# flashlight-driver_2020-10-08_16-01-53.net
KiCad netlist of a schematic drawn in EasyEDA
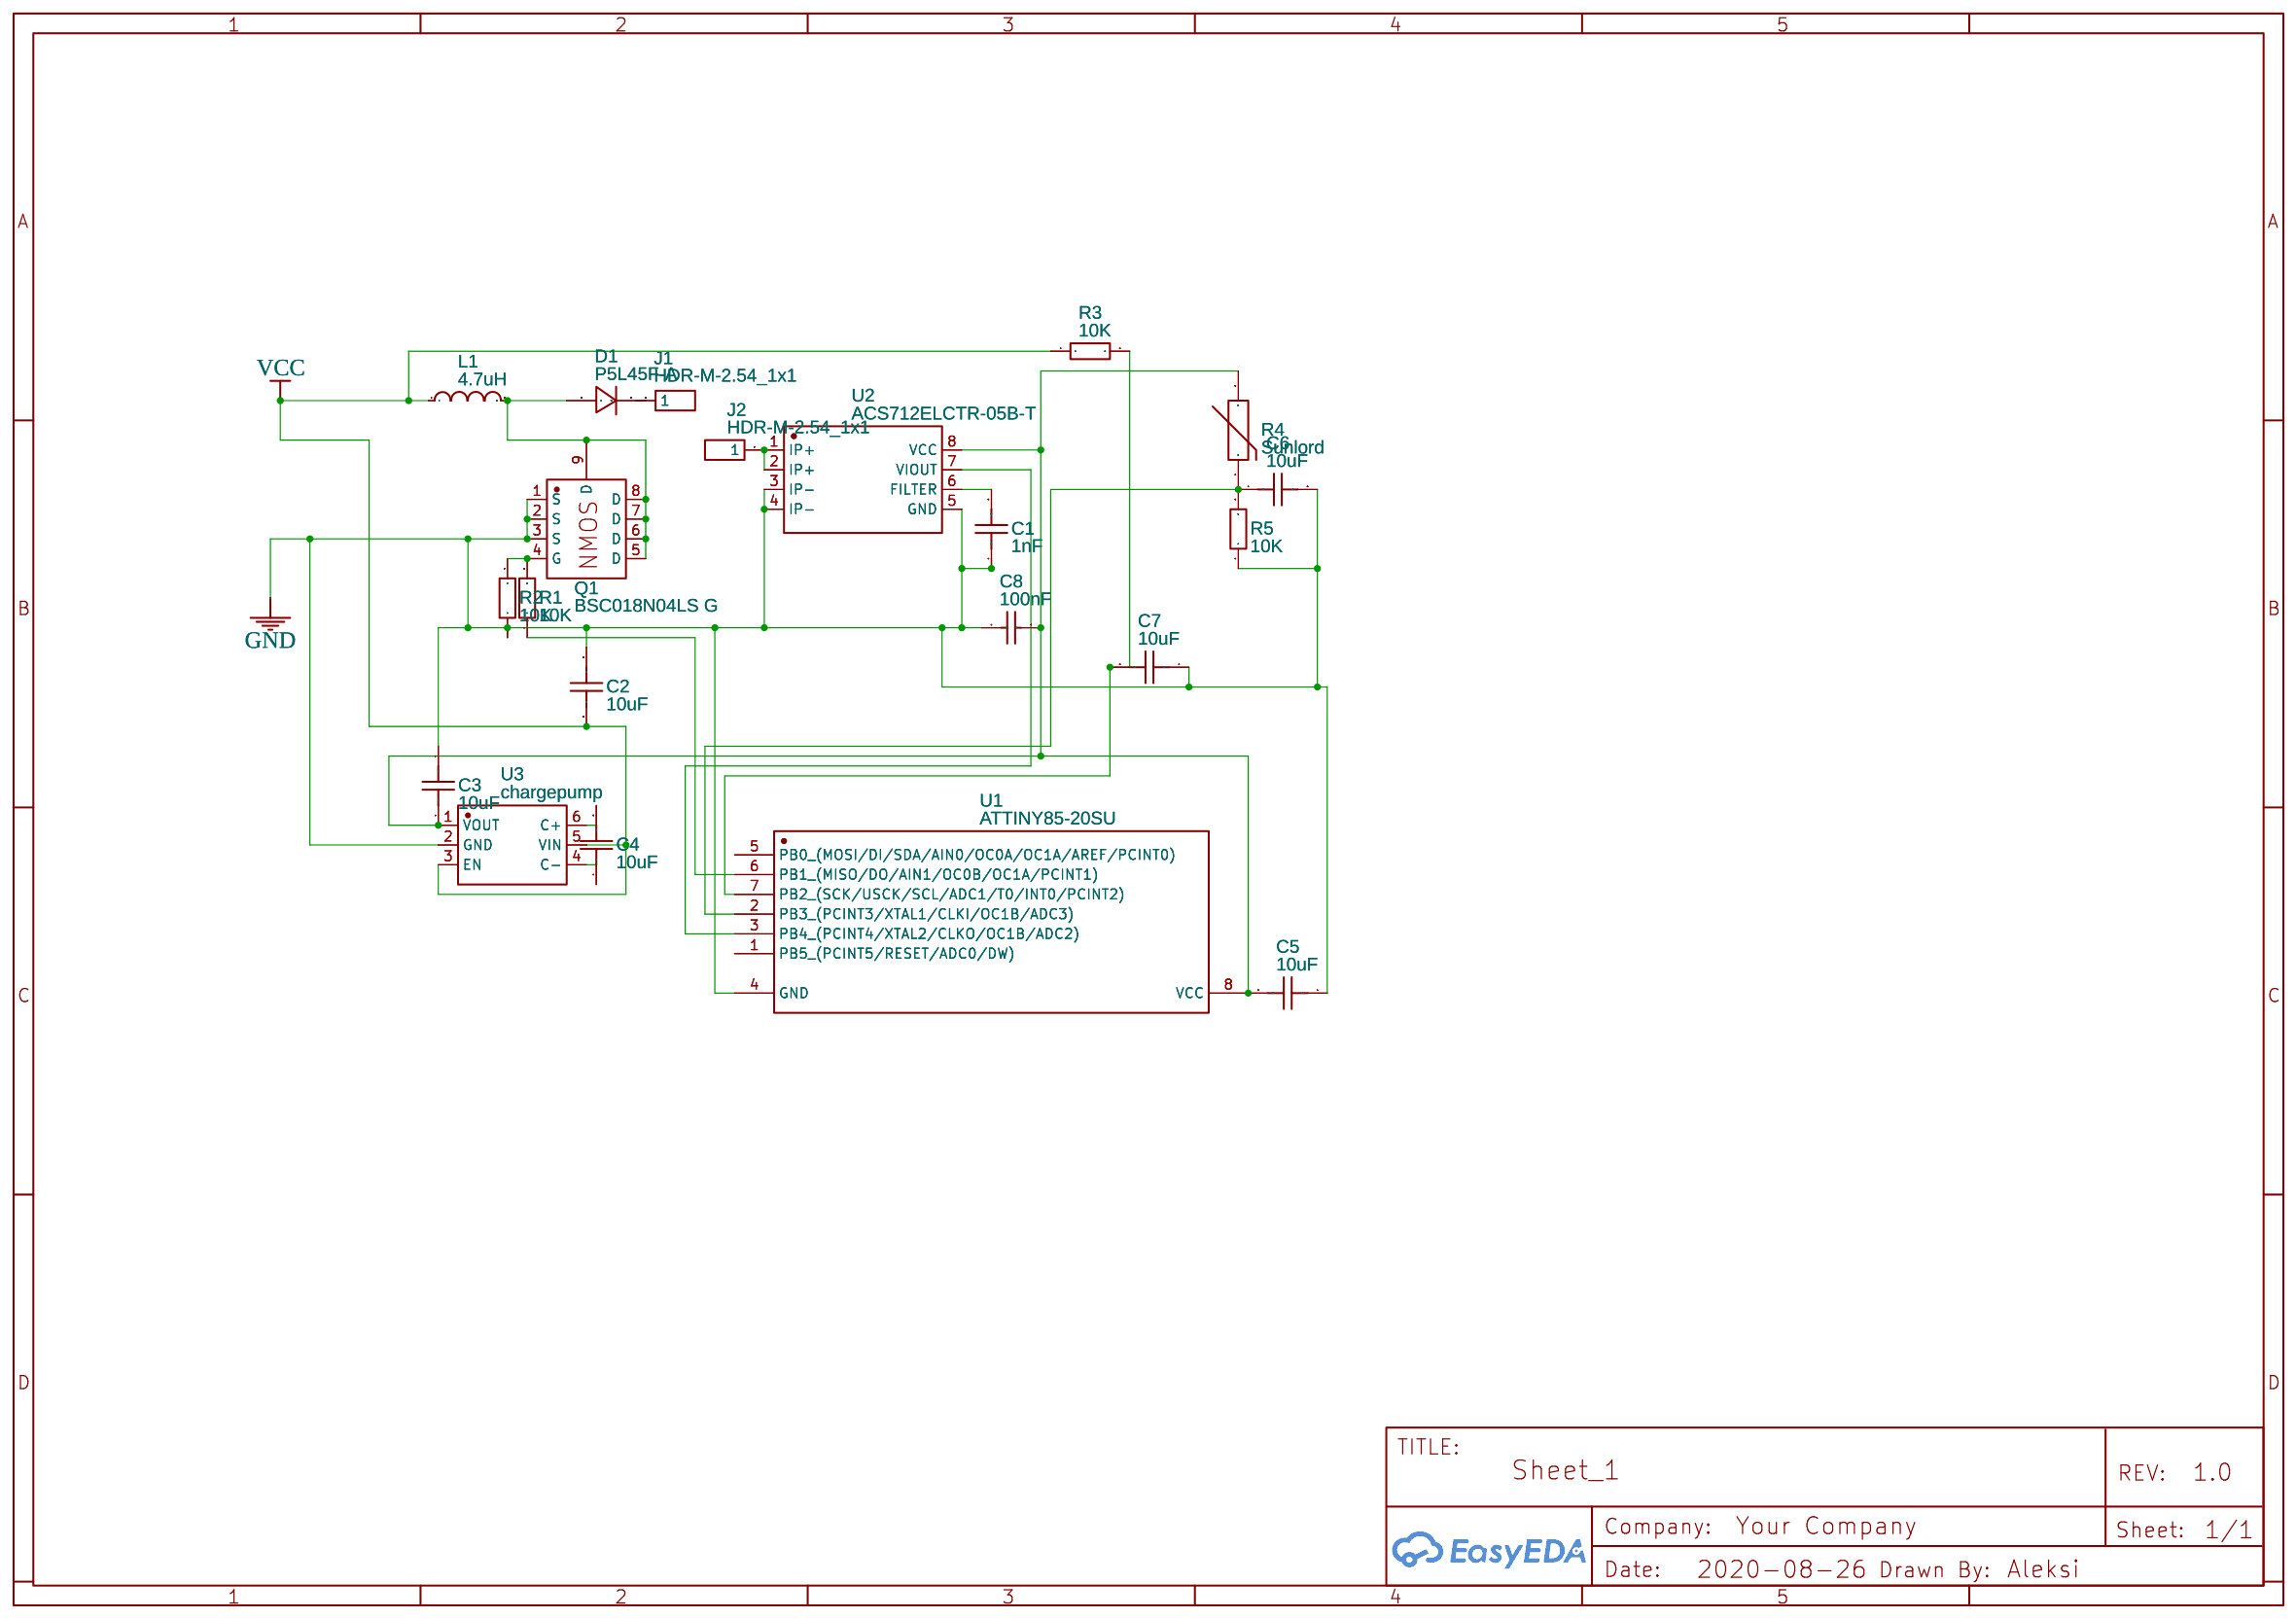
[diagram p0: schematic sheet]

(export (version "E")
  (design (tool "Eeschema 10.0.6"))
  (components
    (comp (ref "C1")
      (value "1nF")
      (fields
        (field (name "BOM_Manufacturer Part") "GRM188R11H102KA01D")
        (field (name "BOM_Supplier Part") "C86007")
      )
      (libsource (lib "") (part "GRM188R11H102KA01D"))
    )
    (comp (ref "C2")
      (value "10uF")
      (fields
        (field (name "BOM_Manufacturer Part") "CL10A106KP8NNNC")
        (field (name "BOM_Supplier Part") "C19702")
      )
      (libsource (lib "") (part "CL10A106KP8NNNC_1"))
    )
    (comp (ref "C3")
      (value "10uF")
      (fields
        (field (name "BOM_Manufacturer Part") "CL10A106KP8NNNC")
        (field (name "BOM_Supplier Part") "C19702")
      )
      (libsource (lib "") (part "CL10A106KP8NNNC_1"))
    )
    (comp (ref "C4")
      (value "10uF")
      (fields
        (field (name "BOM_Manufacturer Part") "CL10A106KP8NNNC")
        (field (name "BOM_Supplier Part") "C19702")
      )
      (libsource (lib "") (part "CL10A106KP8NNNC_1"))
    )
    (comp (ref "C5")
      (value "10uF")
      (fields
        (field (name "BOM_Manufacturer Part") "CL10A106KP8NNNC")
        (field (name "BOM_Supplier Part") "C19702")
      )
      (libsource (lib "") (part "CL10A106KP8NNNC"))
    )
    (comp (ref "C6")
      (value "10uF")
      (fields
        (field (name "BOM_Manufacturer Part") "CL10A106KP8NNNC")
        (field (name "BOM_Supplier Part") "C19702")
      )
      (libsource (lib "") (part "CL10A106KP8NNNC_2"))
    )
    (comp (ref "C7")
      (value "10uF")
      (fields
        (field (name "BOM_Manufacturer Part") "CL10A106KP8NNNC")
        (field (name "BOM_Supplier Part") "C19702")
      )
      (libsource (lib "") (part "CL10A106KP8NNNC"))
    )
    (comp (ref "C8")
      (value "100nF")
      (fields
        (field (name "BOM_Manufacturer Part") "C0603C104K5RACAUTO")
        (field (name "BOM_Supplier Part") "C129621")
      )
      (libsource (lib "") (part "C0603C104K5RACAUTO"))
    )
    (comp (ref "D1")
      (value "P5L45F-A")
      (fields (field (name "BOM_Supplier Part") "C255362"))
      (libsource (lib "") (part "P5L45F-A"))
    )
    (comp (ref "J1")
      (value "HDR-M-2.54_1x1")
      (fields (field (name "BOM_Supplier Part") "C81276"))
      (libsource (lib "") (part "HDR-M-2.54_1x1"))
    )
    (comp (ref "J2")
      (value "HDR-M-2.54_1x1")
      (fields (field (name "BOM_Supplier Part") "C81276"))
      (libsource (lib "") (part "HDR-M-2.54_1x1_1"))
    )
    (comp (ref "L1")
      (value "4.7uH")
      (fields
        (field (name "BOM_Manufacturer Part") "TMAX-1365-4R7-M")
        (field (name "BOM_Supplier Part") "C429830")
      )
      (libsource (lib "") (part "TMAX-1365-4R7-M"))
    )
    (comp (ref "Q1")
      (value "BSC018N04LS G")
      (fields (field (name "BOM_Supplier Part") "C534297"))
      (libsource (lib "") (part "BSC018N04LS G"))
    )
    (comp (ref "R1")
      (value "10K")
      (fields
        (field (name "BOM_Manufacturer Part") "TC0350D1002T5E")
        (field (name "BOM_Supplier Part") "C64266")
      )
      (libsource (lib "") (part "TC0350D1002T5E"))
    )
    (comp (ref "R2")
      (value "10K")
      (fields
        (field (name "BOM_Manufacturer Part") "TC0350D1002T5E")
        (field (name "BOM_Supplier Part") "C64266")
      )
      (libsource (lib "") (part "TC0350D1002T5E"))
    )
    (comp (ref "R3")
      (value "10K")
      (fields
        (field (name "BOM_Manufacturer Part") "TC0350D1002T5E")
        (field (name "BOM_Supplier Part") "C64266")
      )
      (libsource (lib "") (part "TC0350D1002T5E_1"))
    )
    (comp (ref "R4")
      (value "Sunlord")
      (fields
        (field (name "BOM_Manufacturer Part") "SDNT1608X103F3950FTF")
        (field (name "BOM_Supplier Part") "C279936")
      )
      (libsource (lib "") (part "SDNT1608X103F3950FTF"))
    )
    (comp (ref "R5")
      (value "10K")
      (fields
        (field (name "BOM_Manufacturer Part") "TC0350D1002T5E")
        (field (name "BOM_Supplier Part") "C64266")
      )
      (libsource (lib "") (part "TC0350D1002T5E"))
    )
    (comp (ref "U1")
      (value "ATTINY85-20SU")
      (fields (field (name "BOM_Supplier Part") "C89852"))
      (libsource (lib "") (part "ATTINY85-20SU"))
    )
    (comp (ref "U2")
      (value "ACS712ELCTR-05B-T")
      (fields (field (name "BOM_Supplier Part") "C44471"))
      (libsource (lib "") (part "ACS712ELCTR-05B-T"))
    )
    (comp (ref "U3")
      (value "chargepump")
      (fields (field (name "BOM_Manufacturer Part") "10A45"))
      (libsource (lib "") (part "chargepump"))
    )
  )
  (nets
    (net (code "1") (name "GND") (class "Default")
      (node (ref "C1") (pin "1") (pinfunction "1_1") (pintype "unspecified"))
      (node (ref "C2") (pin "2") (pinfunction "2_2") (pintype "unspecified"))
      (node (ref "C3") (pin "2") (pinfunction "2_2") (pintype "unspecified"))
      (node (ref "C5") (pin "1") (pinfunction "1_1") (pintype "unspecified"))
      (node (ref "C6") (pin "2") (pinfunction "2_2") (pintype "unspecified"))
      (node (ref "C7") (pin "1") (pinfunction "1_1") (pintype "unspecified"))
      (node (ref "C8") (pin "1") (pinfunction "1_1") (pintype "input"))
      (node (ref "Q1") (pin "1") (pinfunction "S_1") (pintype "unspecified"))
      (node (ref "Q1") (pin "2") (pinfunction "S_2") (pintype "unspecified"))
      (node (ref "Q1") (pin "3") (pinfunction "S_3") (pintype "unspecified"))
      (node (ref "R2") (pin "1") (pinfunction "1_1") (pintype "input"))
      (node (ref "R5") (pin "1") (pinfunction "1_1") (pintype "input"))
      (node (ref "U1") (pin "4") (pinfunction "GND_4") (pintype "passive"))
      (node (ref "U2") (pin "3") (pinfunction "IP-_3") (pintype "unspecified"))
      (node (ref "U2") (pin "4") (pinfunction "IP-_4") (pintype "unspecified"))
      (node (ref "U2") (pin "5") (pinfunction "GND_5") (pintype "unspecified"))
      (node (ref "U3") (pin "2") (pinfunction "GND_2") (pintype "passive"))
    )
    (net (code "2") (name "Net-(D1-A)") (class "Default")
      (node (ref "D1") (pin "1") (pinfunction "A_1") (pintype "unspecified"))
      (node (ref "L1") (pin "2") (pinfunction "2_2") (pintype "unspecified"))
      (node (ref "Q1") (pin "5") (pinfunction "D_5") (pintype "unspecified"))
      (node (ref "Q1") (pin "6") (pinfunction "D_6") (pintype "unspecified"))
      (node (ref "Q1") (pin "7") (pinfunction "D_7") (pintype "unspecified"))
      (node (ref "Q1") (pin "8") (pinfunction "D_8") (pintype "unspecified"))
      (node (ref "Q1") (pin "9") (pinfunction "D_9") (pintype "unspecified"))
    )
    (net (code "3") (name "Net-(J2-Pad1)") (class "Default")
      (node (ref "J2") (pin "1") (pinfunction "1_1") (pintype "input"))
      (node (ref "U2") (pin "1") (pinfunction "IP+_1") (pintype "unspecified"))
      (node (ref "U2") (pin "2") (pinfunction "IP+_2") (pintype "unspecified"))
    )
    (net (code "4") (name "Net-(Q1-G)") (class "Default")
      (node (ref "Q1") (pin "4") (pinfunction "G_4") (pintype "unspecified"))
      (node (ref "R1") (pin "2") (pinfunction "2_2") (pintype "input"))
      (node (ref "R2") (pin "2") (pinfunction "2_2") (pintype "input"))
    )
    (net (code "5") (name "Net-(U1-PB1_(MISO{slash}DO{slash}AIN1{slash}OC0B{slash}OC1A{slash}PCINT1))") (class "Default")
      (node (ref "R1") (pin "1") (pinfunction "1_1") (pintype "input"))
      (node (ref "U1") (pin "6") (pinfunction "PB1_(MISO/DO/AIN1/OC0B/OC1A/PCINT1)_6") (pintype "bidirectional"))
    )
    (net (code "6") (name "Net-(U1-PB2_(SCK{slash}USCK{slash}SCL{slash}ADC1{slash}T0{slash}INT0{slash}PCINT2))") (class "Default")
      (node (ref "C7") (pin "2") (pinfunction "2_2") (pintype "unspecified"))
      (node (ref "R3") (pin "2") (pinfunction "2_2") (pintype "input"))
      (node (ref "U1") (pin "7") (pinfunction "PB2_(SCK/USCK/SCL/ADC1/T0/INT0/PCINT2)_7") (pintype "bidirectional"))
    )
    (net (code "7") (name "Net-(U1-PB3_(PCINT3{slash}XTAL1{slash}CLKI{slash}OC1B{slash}ADC3))") (class "Default")
      (node (ref "C6") (pin "1") (pinfunction "1_1") (pintype "unspecified"))
      (node (ref "R4") (pin "1") (pinfunction "1_1") (pintype "unspecified"))
      (node (ref "R5") (pin "2") (pinfunction "2_2") (pintype "input"))
      (node (ref "U1") (pin "2") (pinfunction "PB3_(PCINT3/XTAL1/CLKI/OC1B/ADC3)_2") (pintype "bidirectional"))
    )
    (net (code "8") (name "Net-(U1-PB4_(PCINT4{slash}XTAL2{slash}CLKO{slash}OC1B{slash}ADC2))") (class "Default")
      (node (ref "U1") (pin "3") (pinfunction "PB4_(PCINT4/XTAL2/CLKO/OC1B/ADC2)_3") (pintype "bidirectional"))
      (node (ref "U2") (pin "7") (pinfunction "VIOUT_7") (pintype "unspecified"))
    )
    (net (code "9") (name "Net-(U1-VCC)") (class "Default")
      (node (ref "C3") (pin "1") (pinfunction "1_1") (pintype "unspecified"))
      (node (ref "C5") (pin "2") (pinfunction "2_2") (pintype "unspecified"))
      (node (ref "C8") (pin "2") (pinfunction "2_2") (pintype "input"))
      (node (ref "R4") (pin "2") (pinfunction "2_2") (pintype "unspecified"))
      (node (ref "U1") (pin "8") (pinfunction "VCC_8") (pintype "passive"))
      (node (ref "U2") (pin "8") (pinfunction "VCC_8") (pintype "unspecified"))
      (node (ref "U3") (pin "1") (pinfunction "VOUT_1") (pintype "output"))
    )
    (net (code "10") (name "Net-(U2-FILTER)") (class "Default")
      (node (ref "C1") (pin "2") (pinfunction "2_2") (pintype "unspecified"))
      (node (ref "U2") (pin "6") (pinfunction "FILTER_6") (pintype "unspecified"))
    )
    (net (code "11") (name "Net-(U3-C+)") (class "Default")
      (node (ref "C4") (pin "2") (pinfunction "2_2") (pintype "unspecified"))
      (node (ref "U3") (pin "6") (pinfunction "C+_6") (pintype "passive"))
    )
    (net (code "12") (name "Net-(U3-C-)") (class "Default")
      (node (ref "C4") (pin "1") (pinfunction "1_1") (pintype "unspecified"))
      (node (ref "U3") (pin "4") (pinfunction "C-_4") (pintype "passive"))
    )
    (net (code "13") (name "VCC") (class "Default")
      (node (ref "C2") (pin "1") (pinfunction "1_1") (pintype "unspecified"))
      (node (ref "L1") (pin "1") (pinfunction "1_1") (pintype "unspecified"))
      (node (ref "R3") (pin "1") (pinfunction "1_1") (pintype "input"))
      (node (ref "U3") (pin "3") (pinfunction "EN_3") (pintype "input"))
      (node (ref "U3") (pin "5") (pinfunction "VIN_5") (pintype "passive"))
    )
    (net (code "14") (name "unconnected-(D1-C-Pad2)") (class "Default")
      (node (ref "D1") (pin "2") (pinfunction "C_2") (pintype "unspecified"))
    )
    (net (code "15") (name "unconnected-(J1-Pad1)") (class "Default")
      (node (ref "J1") (pin "1") (pinfunction "1_1") (pintype "input"))
    )
    (net (code "16") (name "unconnected-(U1-PB0_(MOSI{slash}DI{slash}SDA{slash}AIN0{slash}OC0A{slash}OC1A{slash}AREF{slash}PCINT0)-Pad5)") (class "Default")
      (node (ref "U1") (pin "5") (pinfunction "PB0_(MOSI/DI/SDA/AIN0/OC0A/OC1A/AREF/PCINT0)_5") (pintype "bidirectional"))
    )
    (net (code "17") (name "unconnected-(U1-PB5_(PCINT5{slash}RESET{slash}ADC0{slash}DW)-Pad1)") (class "Default")
      (node (ref "U1") (pin "1") (pinfunction "PB5_(PCINT5/RESET/ADC0/DW)_1") (pintype "bidirectional"))
    )
  )
)
